# Sheep.net
KiCad netlist of a schematic drawn in EAGLE
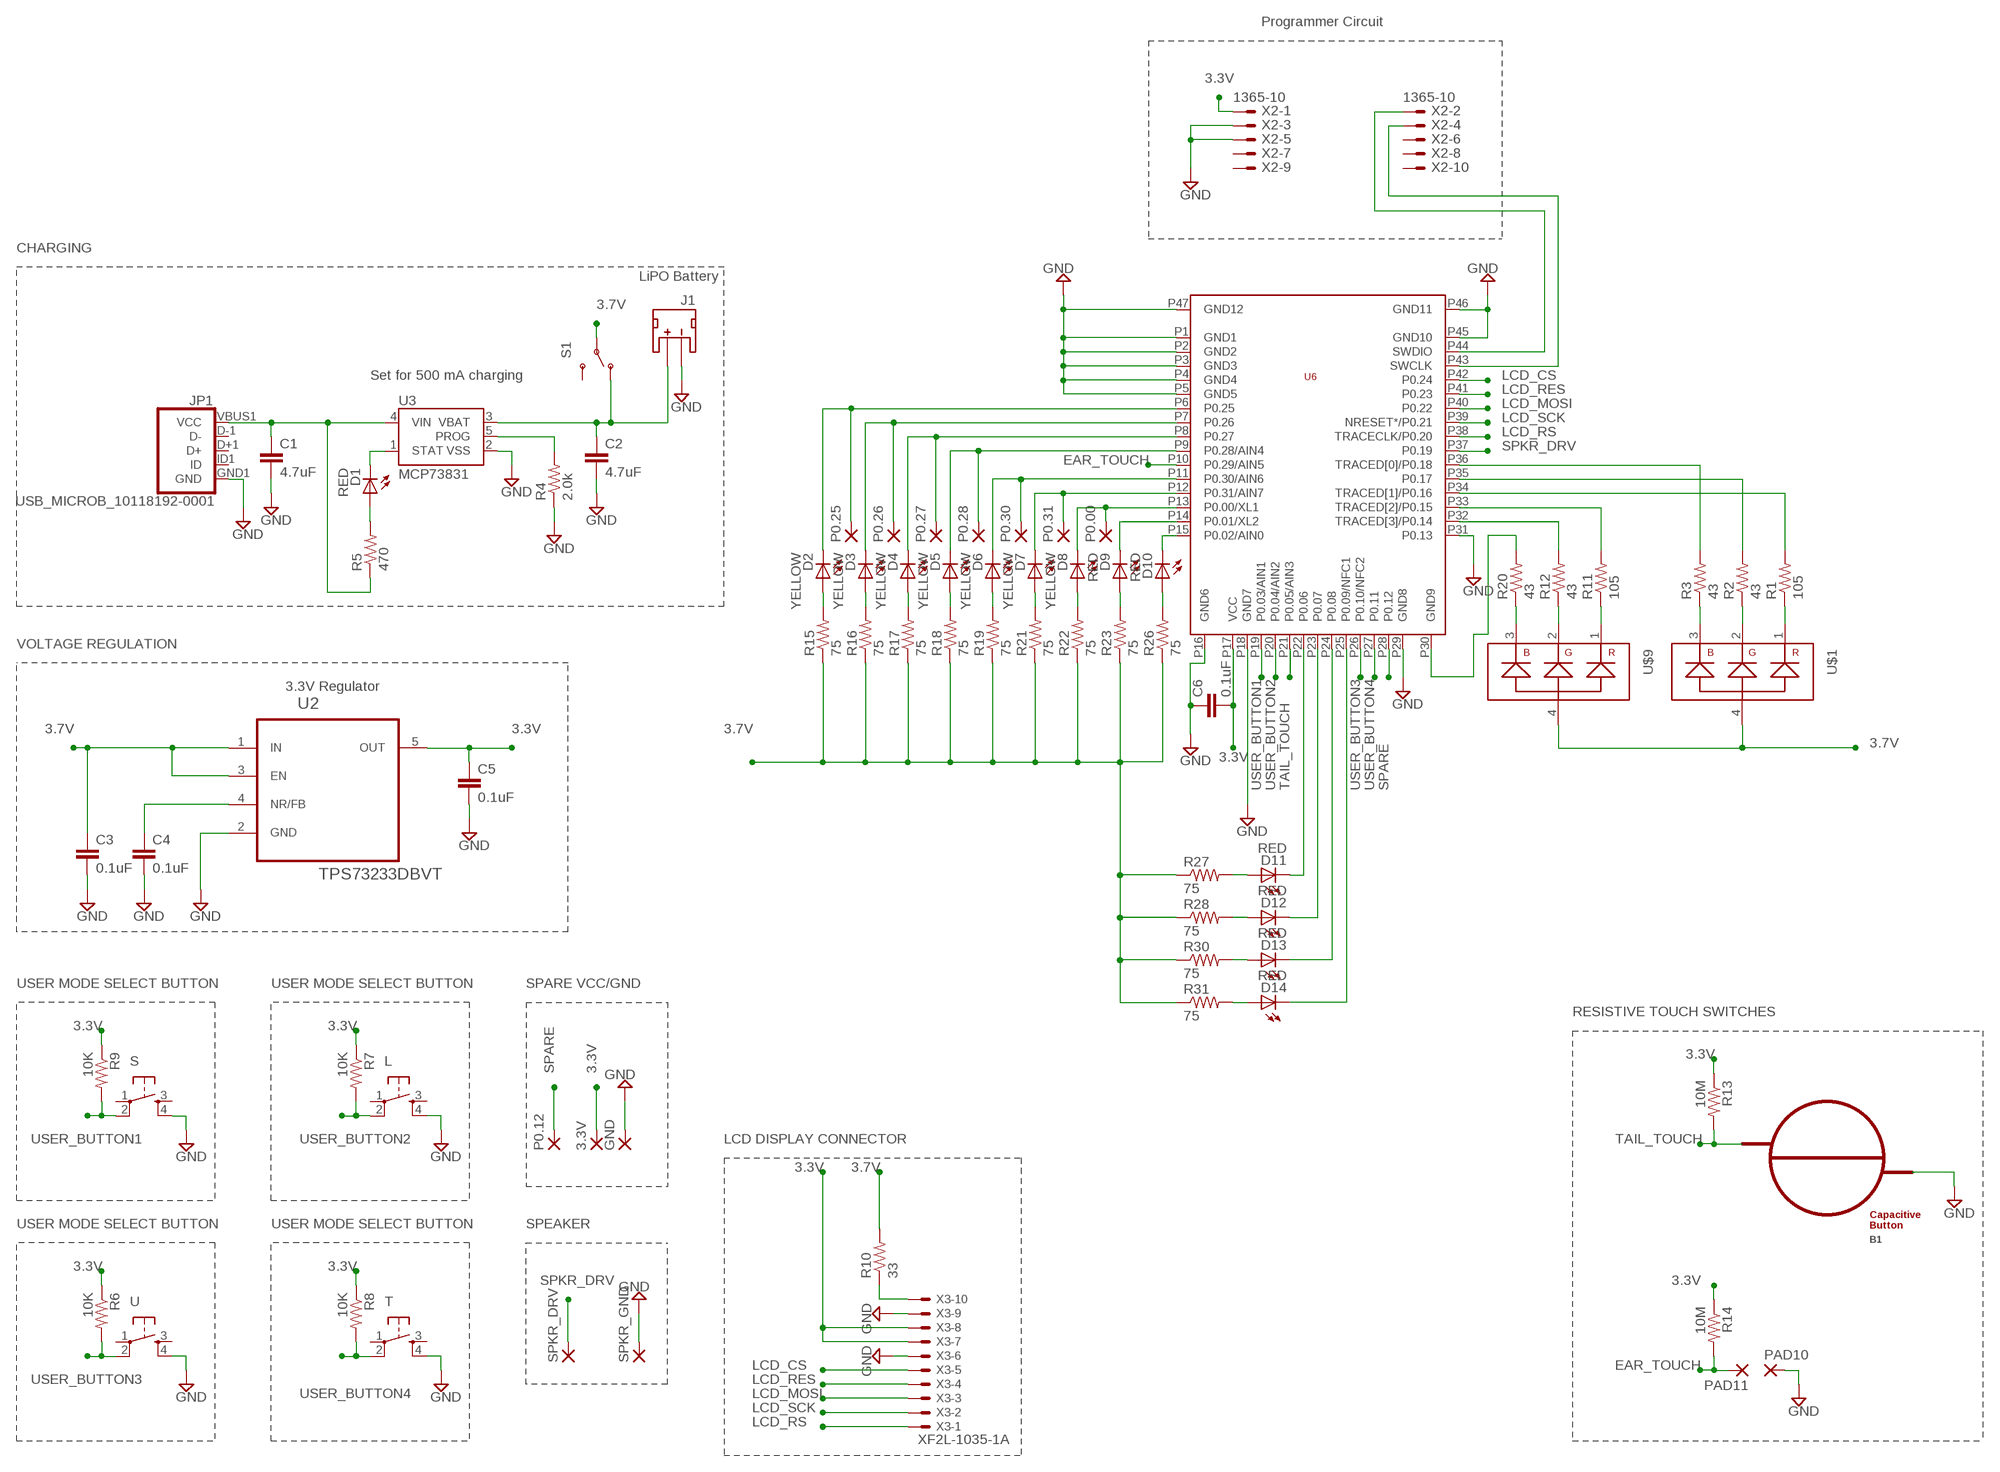
[diagram p0: schematic, sheet 1]

(export (version "E")
  (design (tool "Eeschema 10.0.6"))
  (components
    (comp (ref "3.3V")
      (value "1,6/0,8")
      (footprint "eagle-import:1,6_0,8")
      (libsource (lib "eagle-import") (part "1,6/0,8"))
    )
    (comp (ref "B1")
      (value "BUTTON_ACTIVE_DUAL")
      (footprint "eagle-import:BUTTON_ACTIVE_DUAL_10MM")
      (libsource (lib "eagle-import") (part "BUTTON_ACTIVE_DUAL"))
    )
    (comp (ref "C1")
      (value "4.7uF")
      (footprint "eagle-import:0603-CAP")
      (libsource (lib "eagle-import") (part "CAP0603-CAP"))
    )
    (comp (ref "C2")
      (value "4.7uF")
      (footprint "eagle-import:0603-CAP")
      (libsource (lib "eagle-import") (part "CAP0603-CAP"))
    )
    (comp (ref "C3")
      (value "0.1uF")
      (footprint "eagle-import:C0201")
      (libsource (lib "eagle-import") (part "C-EUC0201"))
    )
    (comp (ref "C4")
      (value "0.1uF")
      (footprint "eagle-import:C0201")
      (libsource (lib "eagle-import") (part "C-EUC0201"))
    )
    (comp (ref "C5")
      (value "0.1uF")
      (footprint "eagle-import:C0201")
      (libsource (lib "eagle-import") (part "C-EUC0201"))
    )
    (comp (ref "C6")
      (value "0.1uF")
      (footprint "eagle-import:C0201")
      (libsource (lib "eagle-import") (part "C-EUC0201"))
    )
    (comp (ref "D1")
      (value "RED")
      (footprint "eagle-import:CHIP-LED0603")
      (libsource (lib "eagle-import") (part "LEDCHIP-LED0603"))
    )
    (comp (ref "D2")
      (value "YELLOW")
      (footprint "eagle-import:CHIP-LED0603")
      (libsource (lib "eagle-import") (part "LEDCHIP-LED0603"))
    )
    (comp (ref "D3")
      (value "YELLOW")
      (footprint "eagle-import:CHIP-LED0603")
      (libsource (lib "eagle-import") (part "LEDCHIP-LED0603"))
    )
    (comp (ref "D4")
      (value "YELLOW")
      (footprint "eagle-import:CHIP-LED0603")
      (libsource (lib "eagle-import") (part "LEDCHIP-LED0603"))
    )
    (comp (ref "D5")
      (value "YELLOW")
      (footprint "eagle-import:CHIP-LED0603")
      (libsource (lib "eagle-import") (part "LEDCHIP-LED0603"))
    )
    (comp (ref "D6")
      (value "YELLOW")
      (footprint "eagle-import:CHIP-LED0603")
      (libsource (lib "eagle-import") (part "LEDCHIP-LED0603"))
    )
    (comp (ref "D7")
      (value "YELLOW")
      (footprint "eagle-import:CHIP-LED0603")
      (libsource (lib "eagle-import") (part "LEDCHIP-LED0603"))
    )
    (comp (ref "D8")
      (value "YELLOW")
      (footprint "eagle-import:CHIP-LED0603")
      (libsource (lib "eagle-import") (part "LEDCHIP-LED0603"))
    )
    (comp (ref "D9")
      (value "RED")
      (footprint "eagle-import:CHIP-LED0603")
      (libsource (lib "eagle-import") (part "LEDCHIP-LED0603"))
    )
    (comp (ref "D10")
      (value "RED")
      (footprint "eagle-import:CHIP-LED0603")
      (libsource (lib "eagle-import") (part "LEDCHIP-LED0603"))
    )
    (comp (ref "D11")
      (value "RED")
      (footprint "eagle-import:CHIP-LED0603")
      (libsource (lib "eagle-import") (part "LEDCHIP-LED0603"))
    )
    (comp (ref "D12")
      (value "RED")
      (footprint "eagle-import:CHIP-LED0603")
      (libsource (lib "eagle-import") (part "LEDCHIP-LED0603"))
    )
    (comp (ref "D13")
      (value "RED")
      (footprint "eagle-import:CHIP-LED0603")
      (libsource (lib "eagle-import") (part "LEDCHIP-LED0603"))
    )
    (comp (ref "D14")
      (value "RED")
      (footprint "eagle-import:CHIP-LED0603")
      (libsource (lib "eagle-import") (part "LEDCHIP-LED0603"))
    )
    (comp (ref "GND")
      (value "1,6/0,8")
      (footprint "eagle-import:1,6_0,8")
      (libsource (lib "eagle-import") (part "1,6/0,8"))
    )
    (comp (ref "J1")
      (value "JST_2MM_MALE")
      (footprint "eagle-import:JST-2-SMD")
      (libsource (lib "eagle-import") (part "JST_2MM_MALE"))
    )
    (comp (ref "JP1")
      (value "USB_MICROB_10118192-0001")
      (footprint "eagle-import:USB-B-MICRO-SMD_V03")
      (libsource (lib "eagle-import") (part "USB_MICROB_PLUGCONN-11752"))
    )
    (comp (ref "L")
      (value "DTSM-6")
      (footprint "eagle-import:DTSM-6")
      (libsource (lib "eagle-import") (part "DTSM-6"))
    )
    (comp (ref "P0.00")
      (value "1,6/0,8")
      (footprint "eagle-import:1,6_0,8")
      (libsource (lib "eagle-import") (part "1,6/0,8"))
    )
    (comp (ref "P0.12")
      (value "1,6/0,8")
      (footprint "eagle-import:1,6_0,8")
      (libsource (lib "eagle-import") (part "1,6/0,8"))
    )
    (comp (ref "P0.25")
      (value "1,6/0,8")
      (footprint "eagle-import:1,6_0,8")
      (libsource (lib "eagle-import") (part "1,6/0,8"))
    )
    (comp (ref "P0.26")
      (value "1,6/0,8")
      (footprint "eagle-import:1,6_0,8")
      (libsource (lib "eagle-import") (part "1,6/0,8"))
    )
    (comp (ref "P0.27")
      (value "1,6/0,8")
      (footprint "eagle-import:1,6_0,8")
      (libsource (lib "eagle-import") (part "1,6/0,8"))
    )
    (comp (ref "P0.28")
      (value "1,6/0,8")
      (footprint "eagle-import:1,6_0,8")
      (libsource (lib "eagle-import") (part "1,6/0,8"))
    )
    (comp (ref "P0.30")
      (value "1,6/0,8")
      (footprint "eagle-import:1,6_0,8")
      (libsource (lib "eagle-import") (part "1,6/0,8"))
    )
    (comp (ref "P0.31")
      (value "1,6/0,8")
      (footprint "eagle-import:1,6_0,8")
      (libsource (lib "eagle-import") (part "1,6/0,8"))
    )
    (comp (ref "PAD10")
      (value "SMD5")
      (footprint "eagle-import:SMD2,54-5,08")
      (libsource (lib "eagle-import") (part "SMD5"))
    )
    (comp (ref "PAD11")
      (value "SMD5")
      (footprint "eagle-import:SMD2,54-5,08")
      (libsource (lib "eagle-import") (part "SMD5"))
    )
    (comp (ref "R1")
      (value "105")
      (footprint "eagle-import:R0201")
      (libsource (lib "eagle-import") (part "R-US_R0201"))
    )
    (comp (ref "R2")
      (value "43")
      (footprint "eagle-import:R0201")
      (libsource (lib "eagle-import") (part "R-US_R0201"))
    )
    (comp (ref "R3")
      (value "43")
      (footprint "eagle-import:R0201")
      (libsource (lib "eagle-import") (part "R-US_R0201"))
    )
    (comp (ref "R4")
      (value "2.0k")
      (footprint "eagle-import:R0201")
      (libsource (lib "eagle-import") (part "R-US_R0201"))
    )
    (comp (ref "R5")
      (value "470")
      (footprint "eagle-import:R0201")
      (libsource (lib "eagle-import") (part "R-US_R0201"))
    )
    (comp (ref "R6")
      (value "10K")
      (footprint "eagle-import:R0201")
      (libsource (lib "eagle-import") (part "R-US_R0201"))
    )
    (comp (ref "R7")
      (value "10K")
      (footprint "eagle-import:R0201")
      (libsource (lib "eagle-import") (part "R-US_R0201"))
    )
    (comp (ref "R8")
      (value "10K")
      (footprint "eagle-import:R0201")
      (libsource (lib "eagle-import") (part "R-US_R0201"))
    )
    (comp (ref "R9")
      (value "10K")
      (footprint "eagle-import:R0201")
      (libsource (lib "eagle-import") (part "R-US_R0201"))
    )
    (comp (ref "R10")
      (value "33")
      (footprint "eagle-import:R0201")
      (libsource (lib "eagle-import") (part "R-US_R0201"))
    )
    (comp (ref "R11")
      (value "105")
      (footprint "eagle-import:R0201")
      (libsource (lib "eagle-import") (part "R-US_R0201"))
    )
    (comp (ref "R12")
      (value "43")
      (footprint "eagle-import:R0201")
      (libsource (lib "eagle-import") (part "R-US_R0201"))
    )
    (comp (ref "R13")
      (value "10M")
      (footprint "eagle-import:R0201")
      (libsource (lib "eagle-import") (part "R-US_R0201"))
    )
    (comp (ref "R14")
      (value "10M")
      (footprint "eagle-import:R0201")
      (libsource (lib "eagle-import") (part "R-US_R0201"))
    )
    (comp (ref "R15")
      (value "75")
      (footprint "eagle-import:R0201")
      (libsource (lib "eagle-import") (part "R-US_R0201"))
    )
    (comp (ref "R16")
      (value "75")
      (footprint "eagle-import:R0201")
      (libsource (lib "eagle-import") (part "R-US_R0201"))
    )
    (comp (ref "R17")
      (value "75")
      (footprint "eagle-import:R0201")
      (libsource (lib "eagle-import") (part "R-US_R0201"))
    )
    (comp (ref "R18")
      (value "75")
      (footprint "eagle-import:R0201")
      (libsource (lib "eagle-import") (part "R-US_R0201"))
    )
    (comp (ref "R19")
      (value "75")
      (footprint "eagle-import:R0201")
      (libsource (lib "eagle-import") (part "R-US_R0201"))
    )
    (comp (ref "R20")
      (value "43")
      (footprint "eagle-import:R0201")
      (libsource (lib "eagle-import") (part "R-US_R0201"))
    )
    (comp (ref "R21")
      (value "75")
      (footprint "eagle-import:R0201")
      (libsource (lib "eagle-import") (part "R-US_R0201"))
    )
    (comp (ref "R22")
      (value "75")
      (footprint "eagle-import:R0201")
      (libsource (lib "eagle-import") (part "R-US_R0201"))
    )
    (comp (ref "R23")
      (value "75")
      (footprint "eagle-import:R0201")
      (libsource (lib "eagle-import") (part "R-US_R0201"))
    )
    (comp (ref "R26")
      (value "75")
      (footprint "eagle-import:R0201")
      (libsource (lib "eagle-import") (part "R-US_R0201"))
    )
    (comp (ref "R27")
      (value "75")
      (footprint "eagle-import:R0201")
      (libsource (lib "eagle-import") (part "R-US_R0201"))
    )
    (comp (ref "R28")
      (value "75")
      (footprint "eagle-import:R0201")
      (libsource (lib "eagle-import") (part "R-US_R0201"))
    )
    (comp (ref "R30")
      (value "75")
      (footprint "eagle-import:R0201")
      (libsource (lib "eagle-import") (part "R-US_R0201"))
    )
    (comp (ref "R31")
      (value "75")
      (footprint "eagle-import:R0201")
      (libsource (lib "eagle-import") (part "R-US_R0201"))
    )
    (comp (ref "S")
      (value "DTSM-6")
      (footprint "eagle-import:DTSM-6")
      (libsource (lib "eagle-import") (part "DTSM-6"))
    )
    (comp (ref "S1")
      (value "SWITCH-SPDTSMD2")
      (footprint "eagle-import:SWITCH-SPDT-SMD")
      (libsource (lib "eagle-import") (part "SWITCH-SPDTSMD2"))
    )
    (comp (ref "SPKR_DRV")
      (value "1,6/0,8")
      (footprint "eagle-import:1,6_0,8")
      (libsource (lib "eagle-import") (part "1,6/0,8"))
    )
    (comp (ref "SPKR_GND")
      (value "1,6/0,8")
      (footprint "eagle-import:1,6_0,8")
      (libsource (lib "eagle-import") (part "1,6/0,8"))
    )
    (comp (ref "T")
      (value "DTSM-6")
      (footprint "eagle-import:DTSM-6")
      (libsource (lib "eagle-import") (part "DTSM-6"))
    )
    (comp (ref "U")
      (value "DTSM-6")
      (footprint "eagle-import:DTSM-6")
      (libsource (lib "eagle-import") (part "DTSM-6"))
    )
    (comp (ref "U$1")
      (value "RGB")
      (footprint "eagle-import:0606")
      (libsource (lib "eagle-import") (part "RGB"))
    )
    (comp (ref "U$9")
      (value "RGB")
      (footprint "eagle-import:0606")
      (libsource (lib "eagle-import") (part "RGB"))
    )
    (comp (ref "U2")
      (value "TPS73233DBVT")
      (footprint "eagle-import:SOT95P280X145-5N")
      (libsource (lib "eagle-import") (part "TPS73233DBVT"))
    )
    (comp (ref "U3")
      (value "MCP73831")
      (footprint "eagle-import:SOT23-5")
      (libsource (lib "eagle-import") (part "MCP73831"))
    )
    (comp (ref "U6")
      (value "BMD-300")
      (footprint "eagle-import:BMD-300")
      (libsource (lib "eagle-import") (part "BMD-300"))
    )
    (comp (ref "X2")
      (value "1365-10")
      (footprint "eagle-import:1365-10")
      (libsource (lib "eagle-import") (part "1365-10"))
    )
    (comp (ref "X3")
      (value "XF2L-1035-1A")
      (footprint "eagle-import:52745-1090")
      (fields (field (name "MPN") "52745-1090"))
      (libsource (lib "eagle-import") (part "52745-1090"))
    )
  )
  (nets
    (net (code "1") (name "/3.3V") (class "Default")
      (node (ref "3.3V") (pin "1") (pinfunction "P_1") (pintype "passive"))
      (node (ref "C5") (pin "1") (pinfunction "1_1") (pintype "passive"))
      (node (ref "C6") (pin "2") (pinfunction "2_2") (pintype "passive"))
      (node (ref "R13") (pin "1") (pinfunction "1_1") (pintype "passive"))
      (node (ref "R14") (pin "1") (pinfunction "1_1") (pintype "passive"))
      (node (ref "R6") (pin "1") (pinfunction "1_1") (pintype "passive"))
      (node (ref "R7") (pin "1") (pinfunction "1_1") (pintype "passive"))
      (node (ref "R8") (pin "1") (pinfunction "1_1") (pintype "passive"))
      (node (ref "R9") (pin "1") (pinfunction "1_1") (pintype "passive"))
      (node (ref "U2") (pin "5") (pinfunction "OUT_5") (pintype "output"))
      (node (ref "U6") (pin "P17") (pinfunction "VCC_P17") (pintype "bidirectional"))
      (node (ref "X2") (pin "1") (pinfunction "S_1") (pintype "passive"))
      (node (ref "X3") (pin "7") (pinfunction "S_7") (pintype "passive"))
      (node (ref "X3") (pin "8") (pinfunction "S_8") (pintype "passive"))
    )
    (net (code "2") (name "/3.7V") (class "Default")
      (node (ref "C3") (pin "1") (pinfunction "1_1") (pintype "passive"))
      (node (ref "R10") (pin "2") (pinfunction "2_2") (pintype "passive"))
      (node (ref "R15") (pin "1") (pinfunction "1_1") (pintype "passive"))
      (node (ref "R16") (pin "1") (pinfunction "1_1") (pintype "passive"))
      (node (ref "R17") (pin "1") (pinfunction "1_1") (pintype "passive"))
      (node (ref "R18") (pin "1") (pinfunction "1_1") (pintype "passive"))
      (node (ref "R19") (pin "1") (pinfunction "1_1") (pintype "passive"))
      (node (ref "R21") (pin "1") (pinfunction "1_1") (pintype "passive"))
      (node (ref "R22") (pin "1") (pinfunction "1_1") (pintype "passive"))
      (node (ref "R23") (pin "1") (pinfunction "1_1") (pintype "passive"))
      (node (ref "R26") (pin "1") (pinfunction "1_1") (pintype "passive"))
      (node (ref "R27") (pin "1") (pinfunction "1_1") (pintype "passive"))
      (node (ref "R28") (pin "1") (pinfunction "1_1") (pintype "passive"))
      (node (ref "R30") (pin "1") (pinfunction "1_1") (pintype "passive"))
      (node (ref "R31") (pin "1") (pinfunction "1_1") (pintype "passive"))
      (node (ref "S1") (pin "2") (pinfunction "P_2") (pintype "passive"))
      (node (ref "U$1") (pin "4") (pinfunction "4_4") (pintype "bidirectional"))
      (node (ref "U$9") (pin "4") (pinfunction "4_4") (pintype "bidirectional"))
      (node (ref "U2") (pin "1") (pinfunction "IN_1") (pintype "power_in"))
      (node (ref "U2") (pin "3") (pinfunction "EN_3") (pintype "input"))
    )
    (net (code "3") (name "/EAR_TOUCH") (class "Default")
      (node (ref "PAD11") (pin "1") (pinfunction "P_1") (pintype "passive"))
      (node (ref "R14") (pin "2") (pinfunction "2_2") (pintype "passive"))
      (node (ref "U6") (pin "P10") (pinfunction "P0.29/AIN5_P10") (pintype "bidirectional"))
    )
    (net (code "4") (name "/LCD_CS") (class "Default")
      (node (ref "U6") (pin "P42") (pinfunction "P0.24_P42") (pintype "bidirectional"))
      (node (ref "X3") (pin "5") (pinfunction "S_5") (pintype "passive"))
    )
    (net (code "5") (name "/LCD_MOSI") (class "Default")
      (node (ref "U6") (pin "P40") (pinfunction "P0.22_P40") (pintype "bidirectional"))
      (node (ref "X3") (pin "3") (pinfunction "S_3") (pintype "passive"))
    )
    (net (code "6") (name "/LCD_RES") (class "Default")
      (node (ref "U6") (pin "P41") (pinfunction "P0.23_P41") (pintype "bidirectional"))
      (node (ref "X3") (pin "4") (pinfunction "S_4") (pintype "passive"))
    )
    (net (code "7") (name "/LCD_RS") (class "Default")
      (node (ref "U6") (pin "P38") (pinfunction "TRACECLK/P0.20_P38") (pintype "bidirectional"))
      (node (ref "X3") (pin "1") (pinfunction "S_1") (pintype "passive"))
    )
    (net (code "8") (name "/LCD_SCK") (class "Default")
      (node (ref "U6") (pin "P39") (pinfunction "NRESET*/P0.21_P39") (pintype "bidirectional"))
      (node (ref "X3") (pin "2") (pinfunction "S_2") (pintype "passive"))
    )
    (net (code "9") (name "/SPARE") (class "Default")
      (node (ref "P0.12") (pin "1") (pinfunction "P_1") (pintype "passive"))
      (node (ref "U6") (pin "P28") (pinfunction "P0.12_P28") (pintype "bidirectional"))
    )
    (net (code "10") (name "/SPKR_DRV") (class "Default")
      (node (ref "SPKR_DRV") (pin "1") (pinfunction "P_1") (pintype "passive"))
      (node (ref "U6") (pin "P37") (pinfunction "P0.19_P37") (pintype "bidirectional"))
    )
    (net (code "11") (name "/TAIL_TOUCH") (class "Default")
      (node (ref "B1") (pin "Q2") (pinfunction "Q2_Q2") (pintype "passive"))
      (node (ref "R13") (pin "2") (pinfunction "2_2") (pintype "passive"))
      (node (ref "U6") (pin "P21") (pinfunction "P0.05/AIN3_P21") (pintype "bidirectional"))
    )
    (net (code "12") (name "/USER_BUTTON1") (class "Default")
      (node (ref "R9") (pin "2") (pinfunction "2_2") (pintype "passive"))
      (node (ref "S") (pin "2") (pinfunction "2_2") (pintype "passive"))
      (node (ref "U6") (pin "P19") (pinfunction "P0.03/AIN1_P19") (pintype "bidirectional"))
    )
    (net (code "13") (name "/USER_BUTTON2") (class "Default")
      (node (ref "L") (pin "2") (pinfunction "2_2") (pintype "passive"))
      (node (ref "R7") (pin "2") (pinfunction "2_2") (pintype "passive"))
      (node (ref "U6") (pin "P20") (pinfunction "P0.04/AIN2_P20") (pintype "bidirectional"))
    )
    (net (code "14") (name "/USER_BUTTON3") (class "Default")
      (node (ref "R6") (pin "2") (pinfunction "2_2") (pintype "passive"))
      (node (ref "U") (pin "2") (pinfunction "2_2") (pintype "passive"))
      (node (ref "U6") (pin "P26") (pinfunction "P0.10/NFC2_P26") (pintype "bidirectional"))
    )
    (net (code "15") (name "/USER_BUTTON4") (class "Default")
      (node (ref "R8") (pin "2") (pinfunction "2_2") (pintype "passive"))
      (node (ref "T") (pin "2") (pinfunction "2_2") (pintype "passive"))
      (node (ref "U6") (pin "P27") (pinfunction "P0.11_P27") (pintype "bidirectional"))
    )
    (net (code "16") (name "GND") (class "Default")
      (node (ref "B1") (pin "Q1") (pinfunction "Q1_Q1") (pintype "passive"))
      (node (ref "C1") (pin "2") (pinfunction "2_2") (pintype "passive"))
      (node (ref "C2") (pin "2") (pinfunction "2_2") (pintype "passive"))
      (node (ref "C3") (pin "2") (pinfunction "2_2") (pintype "passive"))
      (node (ref "C4") (pin "2") (pinfunction "2_2") (pintype "passive"))
      (node (ref "C5") (pin "2") (pinfunction "2_2") (pintype "passive"))
      (node (ref "C6") (pin "1") (pinfunction "1_1") (pintype "passive"))
      (node (ref "GND") (pin "1") (pinfunction "P_1") (pintype "passive"))
      (node (ref "J1") (pin "1") (pinfunction "-_1") (pintype "bidirectional"))
      (node (ref "JP1") (pin "GND1") (pinfunction "GND_GND1") (pintype "bidirectional"))
      (node (ref "L") (pin "4") (pinfunction "4_4") (pintype "passive"))
      (node (ref "PAD10") (pin "1") (pinfunction "P_1") (pintype "passive"))
      (node (ref "R4") (pin "1") (pinfunction "1_1") (pintype "passive"))
      (node (ref "S") (pin "4") (pinfunction "4_4") (pintype "passive"))
      (node (ref "SPKR_GND") (pin "1") (pinfunction "P_1") (pintype "passive"))
      (node (ref "T") (pin "4") (pinfunction "4_4") (pintype "passive"))
      (node (ref "U") (pin "4") (pinfunction "4_4") (pintype "passive"))
      (node (ref "U2") (pin "2") (pinfunction "GND_2") (pintype "passive"))
      (node (ref "U3") (pin "2") (pinfunction "VSS_2") (pintype "power_in"))
      (node (ref "U6") (pin "P1") (pinfunction "GND1_P1") (pintype "bidirectional"))
      (node (ref "U6") (pin "P16") (pinfunction "GND6_P16") (pintype "bidirectional"))
      (node (ref "U6") (pin "P18") (pinfunction "GND7_P18") (pintype "bidirectional"))
      (node (ref "U6") (pin "P2") (pinfunction "GND2_P2") (pintype "bidirectional"))
      (node (ref "U6") (pin "P29") (pinfunction "GND8_P29") (pintype "bidirectional"))
      (node (ref "U6") (pin "P3") (pinfunction "GND3_P3") (pintype "bidirectional"))
      (node (ref "U6") (pin "P31") (pinfunction "P0.13_P31") (pintype "bidirectional"))
      (node (ref "U6") (pin "P4") (pinfunction "GND4_P4") (pintype "bidirectional"))
      (node (ref "U6") (pin "P45") (pinfunction "GND10_P45") (pintype "bidirectional"))
      (node (ref "U6") (pin "P46") (pinfunction "GND11_P46") (pintype "bidirectional"))
      (node (ref "U6") (pin "P47") (pinfunction "GND12_P47") (pintype "bidirectional"))
      (node (ref "U6") (pin "P5") (pinfunction "GND5_P5") (pintype "bidirectional"))
      (node (ref "X2") (pin "3") (pinfunction "S_3") (pintype "passive"))
      (node (ref "X2") (pin "5") (pinfunction "S_5") (pintype "passive"))
      (node (ref "X3") (pin "6") (pinfunction "S_6") (pintype "passive"))
      (node (ref "X3") (pin "9") (pinfunction "S_9") (pintype "passive"))
    )
    (net (code "17") (name "Net-(D1-PadA)") (class "Default")
      (node (ref "D1") (pin "A") (pinfunction "A_A") (pintype "passive"))
      (node (ref "R5") (pin "2") (pinfunction "2_2") (pintype "passive"))
    )
    (net (code "18") (name "Net-(D2-PadA)") (class "Default")
      (node (ref "D2") (pin "A") (pinfunction "A_A") (pintype "passive"))
      (node (ref "R15") (pin "2") (pinfunction "2_2") (pintype "passive"))
    )
    (net (code "19") (name "Net-(D3-PadA)") (class "Default")
      (node (ref "D3") (pin "A") (pinfunction "A_A") (pintype "passive"))
      (node (ref "R16") (pin "2") (pinfunction "2_2") (pintype "passive"))
    )
    (net (code "20") (name "Net-(D4-PadA)") (class "Default")
      (node (ref "D4") (pin "A") (pinfunction "A_A") (pintype "passive"))
      (node (ref "R17") (pin "2") (pinfunction "2_2") (pintype "passive"))
    )
    (net (code "21") (name "Net-(D5-PadA)") (class "Default")
      (node (ref "D5") (pin "A") (pinfunction "A_A") (pintype "passive"))
      (node (ref "R18") (pin "2") (pinfunction "2_2") (pintype "passive"))
    )
    (net (code "22") (name "Net-(D6-PadA)") (class "Default")
      (node (ref "D6") (pin "A") (pinfunction "A_A") (pintype "passive"))
      (node (ref "R19") (pin "2") (pinfunction "2_2") (pintype "passive"))
    )
    (net (code "23") (name "Net-(D7-PadA)") (class "Default")
      (node (ref "D7") (pin "A") (pinfunction "A_A") (pintype "passive"))
      (node (ref "R21") (pin "2") (pinfunction "2_2") (pintype "passive"))
    )
    (net (code "24") (name "Net-(D8-PadA)") (class "Default")
      (node (ref "D8") (pin "A") (pinfunction "A_A") (pintype "passive"))
      (node (ref "R22") (pin "2") (pinfunction "2_2") (pintype "passive"))
    )
    (net (code "25") (name "Net-(D9-PadA)") (class "Default")
      (node (ref "D9") (pin "A") (pinfunction "A_A") (pintype "passive"))
      (node (ref "R23") (pin "2") (pinfunction "2_2") (pintype "passive"))
    )
    (net (code "26") (name "Net-(D10-PadA)") (class "Default")
      (node (ref "D10") (pin "A") (pinfunction "A_A") (pintype "passive"))
      (node (ref "R26") (pin "2") (pinfunction "2_2") (pintype "passive"))
    )
    (net (code "27") (name "Net-(D11-PadA)") (class "Default")
      (node (ref "D11") (pin "A") (pinfunction "A_A") (pintype "passive"))
      (node (ref "R27") (pin "2") (pinfunction "2_2") (pintype "passive"))
    )
    (net (code "28") (name "Net-(D12-PadA)") (class "Default")
      (node (ref "D12") (pin "A") (pinfunction "A_A") (pintype "passive"))
      (node (ref "R28") (pin "2") (pinfunction "2_2") (pintype "passive"))
    )
    (net (code "29") (name "Net-(D13-PadA)") (class "Default")
      (node (ref "D13") (pin "A") (pinfunction "A_A") (pintype "passive"))
      (node (ref "R30") (pin "2") (pinfunction "2_2") (pintype "passive"))
    )
    (net (code "30") (name "Net-(D14-PadA)") (class "Default")
      (node (ref "D14") (pin "A") (pinfunction "A_A") (pintype "passive"))
      (node (ref "R31") (pin "2") (pinfunction "2_2") (pintype "passive"))
    )
    (net (code "31") (name "Net-(J1-+)") (class "Default")
      (node (ref "C2") (pin "1") (pinfunction "1_1") (pintype "passive"))
      (node (ref "J1") (pin "2") (pinfunction "+_2") (pintype "bidirectional"))
      (node (ref "S1") (pin "1") (pinfunction "O_1") (pintype "passive"))
      (node (ref "U3") (pin "3") (pinfunction "VBAT_3") (pintype "power_in"))
    )
    (net (code "32") (name "Net-(JP1-VCC)") (class "Default")
      (node (ref "C1") (pin "1") (pinfunction "1_1") (pintype "passive"))
      (node (ref "JP1") (pin "VBUS1") (pinfunction "VCC_VBUS1") (pintype "bidirectional"))
      (node (ref "R5") (pin "1") (pinfunction "1_1") (pintype "passive"))
      (node (ref "U3") (pin "4") (pinfunction "VIN_4") (pintype "power_in"))
    )
    (net (code "33") (name "Net-(P0.00-P)") (class "Default")
      (node (ref "D8") (pin "C") (pinfunction "C_C") (pintype "passive"))
      (node (ref "P0.00") (pin "1") (pinfunction "P_1") (pintype "passive"))
      (node (ref "U6") (pin "P13") (pinfunction "P0.00/XL1_P13") (pintype "bidirectional"))
    )
    (net (code "34") (name "Net-(P0.25-P)") (class "Default")
      (node (ref "D2") (pin "C") (pinfunction "C_C") (pintype "passive"))
      (node (ref "P0.25") (pin "1") (pinfunction "P_1") (pintype "passive"))
      (node (ref "U6") (pin "P6") (pinfunction "P0.25_P6") (pintype "bidirectional"))
    )
    (net (code "35") (name "Net-(P0.26-P)") (class "Default")
      (node (ref "D3") (pin "C") (pinfunction "C_C") (pintype "passive"))
      (node (ref "P0.26") (pin "1") (pinfunction "P_1") (pintype "passive"))
      (node (ref "U6") (pin "P7") (pinfunction "P0.26_P7") (pintype "bidirectional"))
    )
    (net (code "36") (name "Net-(P0.27-P)") (class "Default")
      (node (ref "D4") (pin "C") (pinfunction "C_C") (pintype "passive"))
      (node (ref "P0.27") (pin "1") (pinfunction "P_1") (pintype "passive"))
      (node (ref "U6") (pin "P8") (pinfunction "P0.27_P8") (pintype "bidirectional"))
    )
    (net (code "37") (name "Net-(P0.28-P)") (class "Default")
      (node (ref "D5") (pin "C") (pinfunction "C_C") (pintype "passive"))
      (node (ref "P0.28") (pin "1") (pinfunction "P_1") (pintype "passive"))
      (node (ref "U6") (pin "P9") (pinfunction "P0.28/AIN4_P9") (pintype "bidirectional"))
    )
    (net (code "38") (name "Net-(P0.30-P)") (class "Default")
      (node (ref "D6") (pin "C") (pinfunction "C_C") (pintype "passive"))
      (node (ref "P0.30") (pin "1") (pinfunction "P_1") (pintype "passive"))
      (node (ref "U6") (pin "P11") (pinfunction "P0.30/AIN6_P11") (pintype "bidirectional"))
    )
    (net (code "39") (name "Net-(P0.31-P)") (class "Default")
      (node (ref "D7") (pin "C") (pinfunction "C_C") (pintype "passive"))
      (node (ref "P0.31") (pin "1") (pinfunction "P_1") (pintype "passive"))
      (node (ref "U6") (pin "P12") (pinfunction "P0.31/AIN7_P12") (pintype "bidirectional"))
    )
    (net (code "40") (name "Net-(R1-Pad1)") (class "Default")
      (node (ref "R1") (pin "1") (pinfunction "1_1") (pintype "passive"))
      (node (ref "U$1") (pin "1") (pinfunction "1_1") (pintype "bidirectional"))
    )
    (net (code "41") (name "Net-(R2-Pad1)") (class "Default")
      (node (ref "R2") (pin "1") (pinfunction "1_1") (pintype "passive"))
      (node (ref "U$1") (pin "2") (pinfunction "2_2") (pintype "bidirectional"))
    )
    (net (code "42") (name "Net-(R3-Pad1)") (class "Default")
      (node (ref "R3") (pin "1") (pinfunction "1_1") (pintype "passive"))
      (node (ref "U$1") (pin "3") (pinfunction "3_3") (pintype "bidirectional"))
    )
    (net (code "43") (name "Net-(R11-Pad1)") (class "Default")
      (node (ref "R11") (pin "1") (pinfunction "1_1") (pintype "passive"))
      (node (ref "U$9") (pin "1") (pinfunction "1_1") (pintype "bidirectional"))
    )
    (net (code "44") (name "Net-(R12-Pad1)") (class "Default")
      (node (ref "R12") (pin "1") (pinfunction "1_1") (pintype "passive"))
      (node (ref "U$9") (pin "2") (pinfunction "2_2") (pintype "bidirectional"))
    )
    (net (code "45") (name "Net-(R20-Pad1)") (class "Default")
      (node (ref "R20") (pin "1") (pinfunction "1_1") (pintype "passive"))
      (node (ref "U$9") (pin "3") (pinfunction "3_3") (pintype "bidirectional"))
    )
    (net (code "46") (name "Net-(U2-NR{slash}FB)") (class "Default")
      (node (ref "C4") (pin "1") (pinfunction "1_1") (pintype "passive"))
      (node (ref "U2") (pin "4") (pinfunction "NR/FB_4") (pintype "input"))
    )
    (net (code "47") (name "Net-(U3-PROG)") (class "Default")
      (node (ref "R4") (pin "2") (pinfunction "2_2") (pintype "passive"))
      (node (ref "U3") (pin "5") (pinfunction "PROG_5") (pintype "input"))
    )
    (net (code "48") (name "Net-(U3-STAT)") (class "Default")
      (node (ref "D1") (pin "C") (pinfunction "C_C") (pintype "passive"))
      (node (ref "U3") (pin "1") (pinfunction "STAT_1") (pintype "output"))
    )
    (net (code "49") (name "Net-(U6-GND9)") (class "Default")
      (node (ref "R20") (pin "2") (pinfunction "2_2") (pintype "passive"))
      (node (ref "U6") (pin "P30") (pinfunction "GND9_P30") (pintype "bidirectional"))
    )
    (net (code "50") (name "Net-(U6-P0.01{slash}XL2)") (class "Default")
      (node (ref "D9") (pin "C") (pinfunction "C_C") (pintype "passive"))
      (node (ref "U6") (pin "P14") (pinfunction "P0.01/XL2_P14") (pintype "bidirectional"))
    )
    (net (code "51") (name "Net-(U6-P0.02{slash}AIN0)") (class "Default")
      (node (ref "D10") (pin "C") (pinfunction "C_C") (pintype "passive"))
      (node (ref "U6") (pin "P15") (pinfunction "P0.02/AIN0_P15") (pintype "bidirectional"))
    )
    (net (code "52") (name "Net-(U6-P0.06)") (class "Default")
      (node (ref "D11") (pin "C") (pinfunction "C_C") (pintype "passive"))
      (node (ref "U6") (pin "P22") (pinfunction "P0.06_P22") (pintype "bidirectional"))
    )
    (net (code "53") (name "Net-(U6-P0.07)") (class "Default")
      (node (ref "D12") (pin "C") (pinfunction "C_C") (pintype "passive"))
      (node (ref "U6") (pin "P23") (pinfunction "P0.07_P23") (pintype "bidirectional"))
    )
    (net (code "54") (name "Net-(U6-P0.08)") (class "Default")
      (node (ref "D13") (pin "C") (pinfunction "C_C") (pintype "passive"))
      (node (ref "U6") (pin "P24") (pinfunction "P0.08_P24") (pintype "bidirectional"))
    )
    (net (code "55") (name "Net-(U6-P0.09{slash}NFC1)") (class "Default")
      (node (ref "D14") (pin "C") (pinfunction "C_C") (pintype "passive"))
      (node (ref "U6") (pin "P25") (pinfunction "P0.09/NFC1_P25") (pintype "bidirectional"))
    )
    (net (code "56") (name "Net-(U6-P0.17)") (class "Default")
      (node (ref "R2") (pin "2") (pinfunction "2_2") (pintype "passive"))
      (node (ref "U6") (pin "P35") (pinfunction "P0.17_P35") (pintype "bidirectional"))
    )
    (net (code "57") (name "Net-(U6-SWCLK)") (class "Default")
      (node (ref "U6") (pin "P43") (pinfunction "SWCLK_P43") (pintype "bidirectional"))
      (node (ref "X2") (pin "4") (pinfunction "S_4") (pintype "passive"))
    )
    (net (code "58") (name "Net-(U6-SWDIO)") (class "Default")
      (node (ref "U6") (pin "P44") (pinfunction "SWDIO_P44") (pintype "bidirectional"))
      (node (ref "X2") (pin "2") (pinfunction "S_2") (pintype "passive"))
    )
    (net (code "59") (name "Net-(U6-TRACED[0]{slash}P0.18)") (class "Default")
      (node (ref "R3") (pin "2") (pinfunction "2_2") (pintype "passive"))
      (node (ref "U6") (pin "P36") (pinfunction "TRACED[0]/P0.18_P36") (pintype "bidirectional"))
    )
    (net (code "60") (name "Net-(U6-TRACED[1]{slash}P0.16)") (class "Default")
      (node (ref "R1") (pin "2") (pinfunction "2_2") (pintype "passive"))
      (node (ref "U6") (pin "P34") (pinfunction "TRACED[1]/P0.16_P34") (pintype "bidirectional"))
    )
    (net (code "61") (name "Net-(U6-TRACED[2]{slash}P0.15)") (class "Default")
      (node (ref "R11") (pin "2") (pinfunction "2_2") (pintype "passive"))
      (node (ref "U6") (pin "P33") (pinfunction "TRACED[2]/P0.15_P33") (pintype "bidirectional"))
    )
    (net (code "62") (name "Net-(U6-TRACED[3]{slash}P0.14)") (class "Default")
      (node (ref "R12") (pin "2") (pinfunction "2_2") (pintype "passive"))
      (node (ref "U6") (pin "P32") (pinfunction "TRACED[3]/P0.14_P32") (pintype "bidirectional"))
    )
    (net (code "63") (name "Net-(X3B-S)") (class "Default")
      (node (ref "R10") (pin "1") (pinfunction "1_1") (pintype "passive"))
      (node (ref "X3") (pin "10") (pinfunction "S_10") (pintype "passive"))
    )
    (net (code "64") (name "unconnected-(J1-PAD1-PadNC1)") (class "Default")
      (node (ref "J1") (pin "NC1") (pinfunction "PAD1_NC1") (pintype "bidirectional"))
    )
    (net (code "65") (name "unconnected-(J1-PAD2-PadNC2)") (class "Default")
      (node (ref "J1") (pin "NC2") (pinfunction "PAD2_NC2") (pintype "bidirectional"))
    )
    (net (code "66") (name "unconnected-(JP1-D+-PadD+1)") (class "Default")
      (node (ref "JP1") (pin "D+1") (pinfunction "D+_D+1") (pintype "bidirectional"))
    )
    (net (code "67") (name "unconnected-(JP1-D--PadD-1)") (class "Default")
      (node (ref "JP1") (pin "D-1") (pinfunction "D-_D-1") (pintype "bidirectional"))
    )
    (net (code "68") (name "unconnected-(JP1-ID-PadID1)") (class "Default")
      (node (ref "JP1") (pin "ID1") (pinfunction "ID_ID1") (pintype "bidirectional"))
    )
    (net (code "69") (name "unconnected-(L-Pad1)") (class "Default")
      (node (ref "L") (pin "1") (pinfunction "1_1") (pintype "passive"))
    )
    (net (code "70") (name "unconnected-(L-Pad3)") (class "Default")
      (node (ref "L") (pin "3") (pinfunction "3_3") (pintype "passive"))
    )
    (net (code "71") (name "unconnected-(S-Pad1)") (class "Default")
      (node (ref "S") (pin "1") (pinfunction "1_1") (pintype "passive"))
    )
    (net (code "72") (name "unconnected-(S-Pad3)") (class "Default")
      (node (ref "S") (pin "3") (pinfunction "3_3") (pintype "passive"))
    )
    (net (code "73") (name "unconnected-(S1-S-Pad3)") (class "Default")
      (node (ref "S1") (pin "3") (pinfunction "S_3") (pintype "passive"))
    )
    (net (code "74") (name "unconnected-(T-Pad1)") (class "Default")
      (node (ref "T") (pin "1") (pinfunction "1_1") (pintype "passive"))
    )
    (net (code "75") (name "unconnected-(T-Pad3)") (class "Default")
      (node (ref "T") (pin "3") (pinfunction "3_3") (pintype "passive"))
    )
    (net (code "76") (name "unconnected-(U-Pad1)") (class "Default")
      (node (ref "U") (pin "1") (pinfunction "1_1") (pintype "passive"))
    )
    (net (code "77") (name "unconnected-(U-Pad3)") (class "Default")
      (node (ref "U") (pin "3") (pinfunction "3_3") (pintype "passive"))
    )
    (net (code "78") (name "unconnected-(X2B-S-Pad10)") (class "Default")
      (node (ref "X2") (pin "10") (pinfunction "S_10") (pintype "passive"))
    )
    (net (code "79") (name "unconnected-(X2G-S-Pad6)") (class "Default")
      (node (ref "X2") (pin "6") (pinfunction "S_6") (pintype "passive"))
    )
    (net (code "80") (name "unconnected-(X2H-S-Pad7)") (class "Default")
      (node (ref "X2") (pin "7") (pinfunction "S_7") (pintype "passive"))
    )
    (net (code "81") (name "unconnected-(X2I-S-Pad8)") (class "Default")
      (node (ref "X2") (pin "8") (pinfunction "S_8") (pintype "passive"))
    )
    (net (code "82") (name "unconnected-(X2J-S-Pad9)") (class "Default")
      (node (ref "X2") (pin "9") (pinfunction "S_9") (pintype "passive"))
    )
  )
)
